# Motor_Driver.net
KiCad netlist of a schematic drawn in Altium Designer
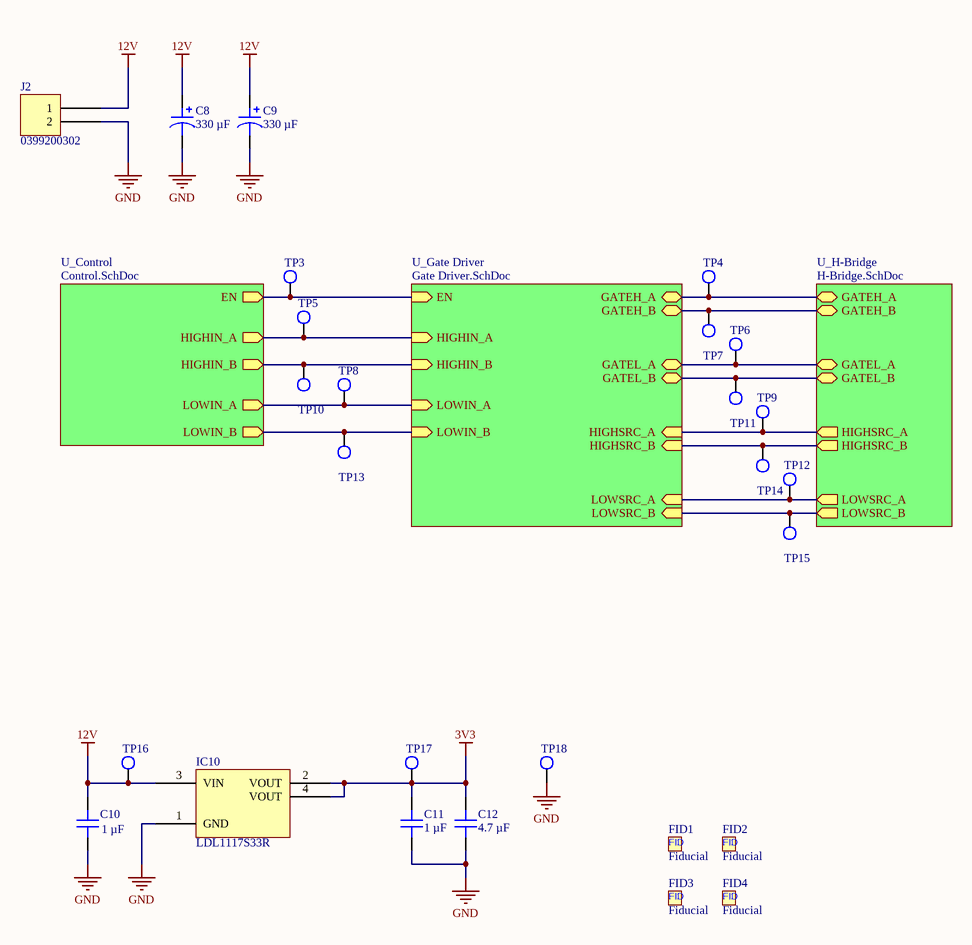
[diagram p0: Motor Driver.SchDoc]

(export (version "E")
  (design (tool "Eeschema 10.0.6"))
  (components
    (comp (ref "C8")
      (value "330 µF")
      (footprint "CAP TH ALPOLY D10.00mm S5.00mm H13.50mm")
      (description "CAP ALUM POLY 330UF 20% 35V T/H")
      (fields (field (name "PART NUMBER") "337AVG035MGBJ") (field (name "MANUFACTURER") "Illinois Capacitor"))
      (libsource (lib "altiumlibrary.com") (part "Polarised Capacitor"))
    )
    (comp (ref "C9")
      (value "330 µF")
      (footprint "CAP TH ALPOLY D10.00mm S5.00mm H13.50mm")
      (description "CAP ALUM POLY 330UF 20% 35V T/H")
      (fields (field (name "PART NUMBER") "337AVG035MGBJ") (field (name "MANUFACTURER") "Illinois Capacitor"))
      (libsource (lib "altiumlibrary.com") (part "Polarised Capacitor"))
    )
    (comp (ref "C10")
      (value "1 µF")
      (footprint "CAP 0805_2012")
      (description "CAP CER 1UF 50V X7R 0805")
      (fields (field (name "PART NUMBER") "08055C105KAZ2A") (field (name "MANUFACTURER") "KYOCERA AVX"))
      (libsource (lib "altiumlibrary.com") (part "Capacitor"))
    )
    (comp (ref "C11")
      (value "1 µF")
      (footprint "CAP 0805_2012")
      (description "CAP CER 1UF 50V X7R 0805")
      (fields (field (name "PART NUMBER") "08055C105KAZ2A") (field (name "MANUFACTURER") "KYOCERA AVX"))
      (libsource (lib "altiumlibrary.com") (part "Capacitor"))
    )
    (comp (ref "C12")
      (value "4.7 µF")
      (footprint "CAP 0805_2012")
      (description "CAP CER 4.7UF 10V X5R 0805")
      (fields (field (name "PART NUMBER") "885012107009") (field (name "MANUFACTURER") "Würth Elektronik"))
      (libsource (lib "altiumlibrary.com") (part "Capacitor"))
    )
    (comp (ref "FID1")
      (value "Fiducial")
      (footprint "Fiducial-1mm")
      (libsource (lib "CelestialUseful") (part "Fiducial"))
    )
    (comp (ref "FID2")
      (value "Fiducial")
      (footprint "Fiducial-1mm")
      (libsource (lib "CelestialUseful") (part "Fiducial"))
    )
    (comp (ref "FID3")
      (value "Fiducial")
      (footprint "Fiducial-1mm")
      (libsource (lib "CelestialUseful") (part "Fiducial"))
    )
    (comp (ref "FID4")
      (value "Fiducial")
      (footprint "Fiducial-1mm")
      (libsource (lib "CelestialUseful") (part "Fiducial"))
    )
    (comp (ref "IC10")
      (value "LDL1117S33R")
      (footprint "ST SOT-223")
      (description "IC REG LINEAR 3.3V 1.2A SOT223")
      (fields (field (name "MANUFACTURER") "STMicroelectronics"))
      (libsource (lib "altiumlibrary.com") (part "ST LDL1117"))
    )
    (comp (ref "J2")
      (value "0399200302")
      (footprint "MOLEX 0399200302")
      (description "TERM BLK 2P SIDE ENTRY 15MM PCB")
      (fields (field (name "MANUFACTURER") "Molex") (field (name "VOLTAGE") "600 V"))
      (libsource (lib "altiumlibrary.com") (part "2 Pin"))
    )
    (comp (ref "TP3")
      (value "Test Point")
      (footprint "TestPoint-1.5mm")
      (libsource (lib "CelestialUseful") (part "Test Point"))
    )
    (comp (ref "TP4")
      (value "Test Point")
      (footprint "TestPoint-1.5mm")
      (libsource (lib "CelestialUseful") (part "Test Point"))
    )
    (comp (ref "TP5")
      (value "Test Point")
      (footprint "TestPoint-1.5mm")
      (libsource (lib "CelestialUseful") (part "Test Point"))
    )
    (comp (ref "TP6")
      (value "Test Point")
      (footprint "TestPoint-1.5mm")
      (libsource (lib "CelestialUseful") (part "Test Point"))
    )
    (comp (ref "TP7")
      (value "Test Point")
      (footprint "TestPoint-1.5mm")
      (libsource (lib "CelestialUseful") (part "Test Point"))
    )
    (comp (ref "TP8")
      (value "Test Point")
      (footprint "TestPoint-1.5mm")
      (libsource (lib "CelestialUseful") (part "Test Point"))
    )
    (comp (ref "TP9")
      (value "Test Point")
      (footprint "TestPoint-1.5mm")
      (libsource (lib "CelestialUseful") (part "Test Point"))
    )
    (comp (ref "TP10")
      (value "Test Point")
      (footprint "TestPoint-1.5mm")
      (libsource (lib "CelestialUseful") (part "Test Point"))
    )
    (comp (ref "TP11")
      (value "Test Point")
      (footprint "TestPoint-1.5mm")
      (libsource (lib "CelestialUseful") (part "Test Point"))
    )
    (comp (ref "TP12")
      (value "Test Point")
      (footprint "TestPoint-1.5mm")
      (libsource (lib "CelestialUseful") (part "Test Point"))
    )
    (comp (ref "TP13")
      (value "Test Point")
      (footprint "TestPoint-1.5mm")
      (libsource (lib "CelestialUseful") (part "Test Point"))
    )
    (comp (ref "TP14")
      (value "Test Point")
      (footprint "TestPoint-1.5mm")
      (libsource (lib "CelestialUseful") (part "Test Point"))
    )
    (comp (ref "TP15")
      (value "Test Point")
      (footprint "TestPoint-1.5mm")
      (libsource (lib "CelestialUseful") (part "Test Point"))
    )
    (comp (ref "TP16")
      (value "Test Point")
      (footprint "TestPoint-1.5mm")
      (libsource (lib "CelestialUseful") (part "Test Point"))
    )
    (comp (ref "TP17")
      (value "Test Point")
      (footprint "TestPoint-1.5mm")
      (libsource (lib "CelestialUseful") (part "Test Point"))
    )
    (comp (ref "TP18")
      (value "Test Point")
      (footprint "TestPoint-1.5mm")
      (libsource (lib "CelestialUseful") (part "Test Point"))
    )
  )
  (nets
    (net (code "1") (name "/EN") (class "Default")
      (node (ref "TP3") (pin "1") (pinfunction "TP_1") (pintype "passive"))
    )
    (net (code "2") (name "/GATEH_A") (class "Default")
      (node (ref "TP4") (pin "1") (pinfunction "TP_1") (pintype "passive"))
    )
    (net (code "3") (name "/GATEH_B") (class "Default")
      (node (ref "TP7") (pin "1") (pinfunction "TP_1") (pintype "passive"))
    )
    (net (code "4") (name "/GATEL_A") (class "Default")
      (node (ref "TP6") (pin "1") (pinfunction "TP_1") (pintype "passive"))
    )
    (net (code "5") (name "/GATEL_B") (class "Default")
      (node (ref "TP11") (pin "1") (pinfunction "TP_1") (pintype "passive"))
    )
    (net (code "6") (name "/HIGHIN_A") (class "Default")
      (node (ref "TP5") (pin "1") (pinfunction "TP_1") (pintype "passive"))
    )
    (net (code "7") (name "/HIGHIN_B") (class "Default")
      (node (ref "TP10") (pin "1") (pinfunction "TP_1") (pintype "passive"))
    )
    (net (code "8") (name "/HIGHSRC_A") (class "Default")
      (node (ref "TP9") (pin "1") (pinfunction "TP_1") (pintype "passive"))
    )
    (net (code "9") (name "/HIGHSRC_B") (class "Default")
      (node (ref "TP14") (pin "1") (pinfunction "TP_1") (pintype "passive"))
    )
    (net (code "10") (name "/LOWIN_A") (class "Default")
      (node (ref "TP8") (pin "1") (pinfunction "TP_1") (pintype "passive"))
    )
    (net (code "11") (name "/LOWIN_B") (class "Default")
      (node (ref "TP13") (pin "1") (pinfunction "TP_1") (pintype "passive"))
    )
    (net (code "12") (name "/LOWSRC_A") (class "Default")
      (node (ref "TP12") (pin "1") (pinfunction "TP_1") (pintype "passive"))
    )
    (net (code "13") (name "/LOWSRC_B") (class "Default")
      (node (ref "TP15") (pin "1") (pinfunction "TP_1") (pintype "passive"))
    )
    (net (code "14") (name "3V3") (class "Default")
      (node (ref "C11") (pin "2") (pinfunction "2_2") (pintype "passive"))
      (node (ref "C12") (pin "2") (pinfunction "2_2") (pintype "passive"))
      (node (ref "IC10") (pin "2") (pinfunction "VOUT_2") (pintype "passive"))
      (node (ref "IC10") (pin "4") (pinfunction "VOUT_4") (pintype "passive"))
      (node (ref "TP17") (pin "1") (pinfunction "TP_1") (pintype "passive"))
    )
    (net (code "15") (name "12V") (class "Default")
      (node (ref "C10") (pin "2") (pinfunction "2_2") (pintype "passive"))
      (node (ref "C8") (pin "1") (pinfunction "1_1") (pintype "passive"))
      (node (ref "C9") (pin "1") (pinfunction "1_1") (pintype "passive"))
      (node (ref "IC10") (pin "3") (pinfunction "VIN_3") (pintype "passive"))
      (node (ref "J2") (pin "1") (pinfunction "1_1") (pintype "passive"))
      (node (ref "TP16") (pin "1") (pinfunction "TP_1") (pintype "passive"))
    )
    (net (code "16") (name "GND") (class "Default")
      (node (ref "C10") (pin "1") (pinfunction "1_1") (pintype "passive"))
      (node (ref "C11") (pin "1") (pinfunction "1_1") (pintype "passive"))
      (node (ref "C12") (pin "1") (pinfunction "1_1") (pintype "passive"))
      (node (ref "C8") (pin "2") (pinfunction "2_2") (pintype "passive"))
      (node (ref "C9") (pin "2") (pinfunction "2_2") (pintype "passive"))
      (node (ref "IC10") (pin "1") (pinfunction "GND_1") (pintype "passive"))
      (node (ref "J2") (pin "2") (pinfunction "2_2") (pintype "passive"))
      (node (ref "TP18") (pin "1") (pinfunction "TP_1") (pintype "passive"))
    )
  )
)
